# LilyPad-reed.net
KiCad netlist of a schematic drawn in EAGLE
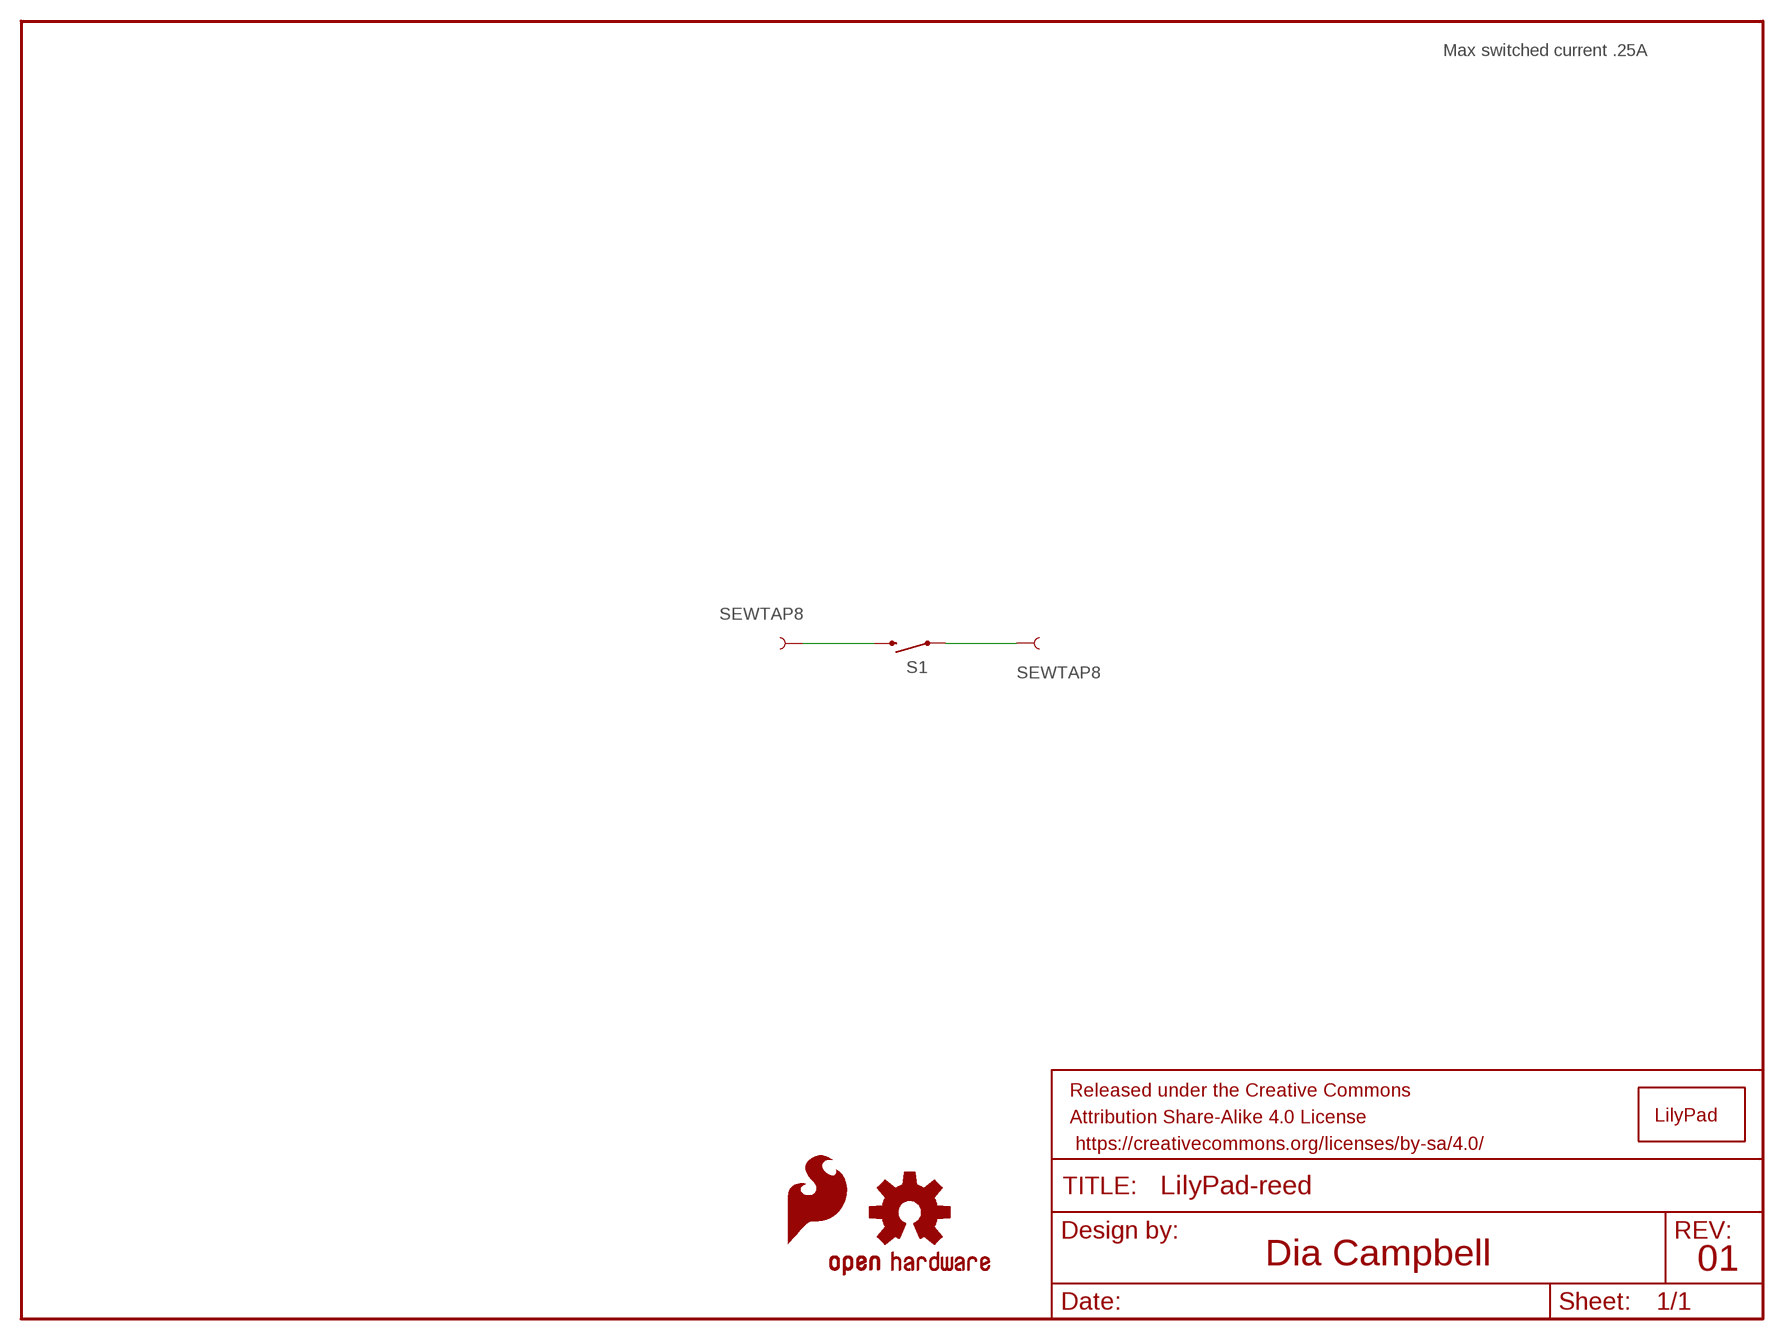
[diagram p0: schematic, sheet 1]

(export (version "E")
  (design (tool "Eeschema 10.0.6"))
  (components
    (comp (ref "FRAME1")
      (value "FRAME-LETTER")
      (footprint "eagle-import:CREATIVE_COMMONS")
      (fields (field (name "DESIGNER") "NAME"))
      (libsource (lib "eagle-import") (part "FRAME-LETTER"))
    )
    (comp (ref "LOGO1")
      (value "OSHW-LOGOS-COPPER")
      (footprint "eagle-import:OSHW-LOGO-S_COPPER")
      (libsource (lib "eagle-import") (part "OSHW-LOGOS-COPPER"))
    )
    (comp (ref "LOGO2")
      (value "SFE_LOGO_FLAME.1COP")
      (footprint "eagle-import:SFE_LOGO_FLAME_COPPER_.1")
      (libsource (lib "eagle-import") (part "SFE_LOGO_FLAME.1COP"))
    )
    (comp (ref "S1")
      (value "REED")
      (footprint "eagle-import:REED_SWITCH_PLASTIC")
      (libsource (lib "eagle-import") (part "SWITCH-MOMENTARY-2PTH_REED2"))
    )
    (comp (ref "SLIDEOFF")
      (value "SEWTAP8")
      (footprint "eagle-import:PETAL-MEDIUM-2SIDE")
      (libsource (lib "eagle-import") (part "SEWTAP8"))
    )
    (comp (ref "SLIDEON")
      (value "SEWTAP8")
      (footprint "eagle-import:PETAL-MEDIUM-2SIDE")
      (libsource (lib "eagle-import") (part "SEWTAP8"))
    )
    (comp (ref "U$1")
      (value "LOGO-LPLP")
      (footprint "eagle-import:LOGO-LILYPAD")
      (libsource (lib "eagle-import") (part "LOGO-LPLP"))
    )
  )
  (nets
    (net (code "1") (name "Net-(S1-1)") (class "Default")
      (node (ref "S1") (pin "P$1") (pinfunction "1_P$1") (pintype "passive"))
      (node (ref "SLIDEON") (pin "1") (pinfunction "1_1") (pintype "bidirectional"))
    )
    (net (code "2") (name "Net-(S1-2)") (class "Default")
      (node (ref "S1") (pin "P$2") (pinfunction "2_P$2") (pintype "passive"))
      (node (ref "SLIDEOFF") (pin "1") (pinfunction "1_1") (pintype "bidirectional"))
    )
  )
)
